# mh_stepper_con.net
KiCad netlist of a schematic drawn in EAGLE
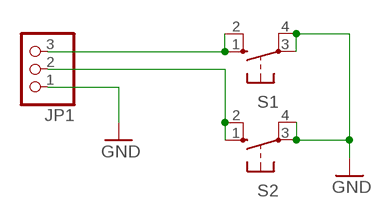
[diagram p0: schematic, sheet 1]

(export (version "E")
  (design (tool "Eeschema 10.0.6"))
  (components
    (comp (ref "JP1")
      (value "PINHD-1X3")
      (footprint "eagle-import:1X03")
      (libsource (lib "eagle-import") (part "PINHD-1X3"))
    )
    (comp (ref "S1")
      (value "10-XX")
      (footprint "eagle-import:B3F-10XX")
      (fields (field (name "MPN") "B3F-1000"))
      (libsource (lib "eagle-import") (part "10-XX"))
    )
    (comp (ref "S2")
      (value "10-XX")
      (footprint "eagle-import:B3F-10XX")
      (fields (field (name "MPN") "B3F-1000"))
      (libsource (lib "eagle-import") (part "10-XX"))
    )
  )
  (nets
    (net (code "1") (name "GND") (class "Default")
      (node (ref "JP1") (pin "1") (pinfunction "1_1") (pintype "passive"))
      (node (ref "S1") (pin "3") (pinfunction "P_3") (pintype "passive"))
      (node (ref "S1") (pin "4") (pinfunction "P1_4") (pintype "passive"))
      (node (ref "S2") (pin "3") (pinfunction "P_3") (pintype "passive"))
      (node (ref "S2") (pin "4") (pinfunction "P1_4") (pintype "passive"))
    )
    (net (code "2") (name "Net-(S1-S)") (class "Default")
      (node (ref "JP1") (pin "3") (pinfunction "3_3") (pintype "passive"))
      (node (ref "S1") (pin "1") (pinfunction "S_1") (pintype "passive"))
      (node (ref "S1") (pin "2") (pinfunction "S1_2") (pintype "passive"))
    )
    (net (code "3") (name "Net-(S2-S)") (class "Default")
      (node (ref "JP1") (pin "2") (pinfunction "2_2") (pintype "passive"))
      (node (ref "S2") (pin "1") (pinfunction "S_1") (pintype "passive"))
      (node (ref "S2") (pin "2") (pinfunction "S1_2") (pintype "passive"))
    )
  )
)
